# main_board_schematic.net
KiCad netlist of a schematic drawn in EasyEDA
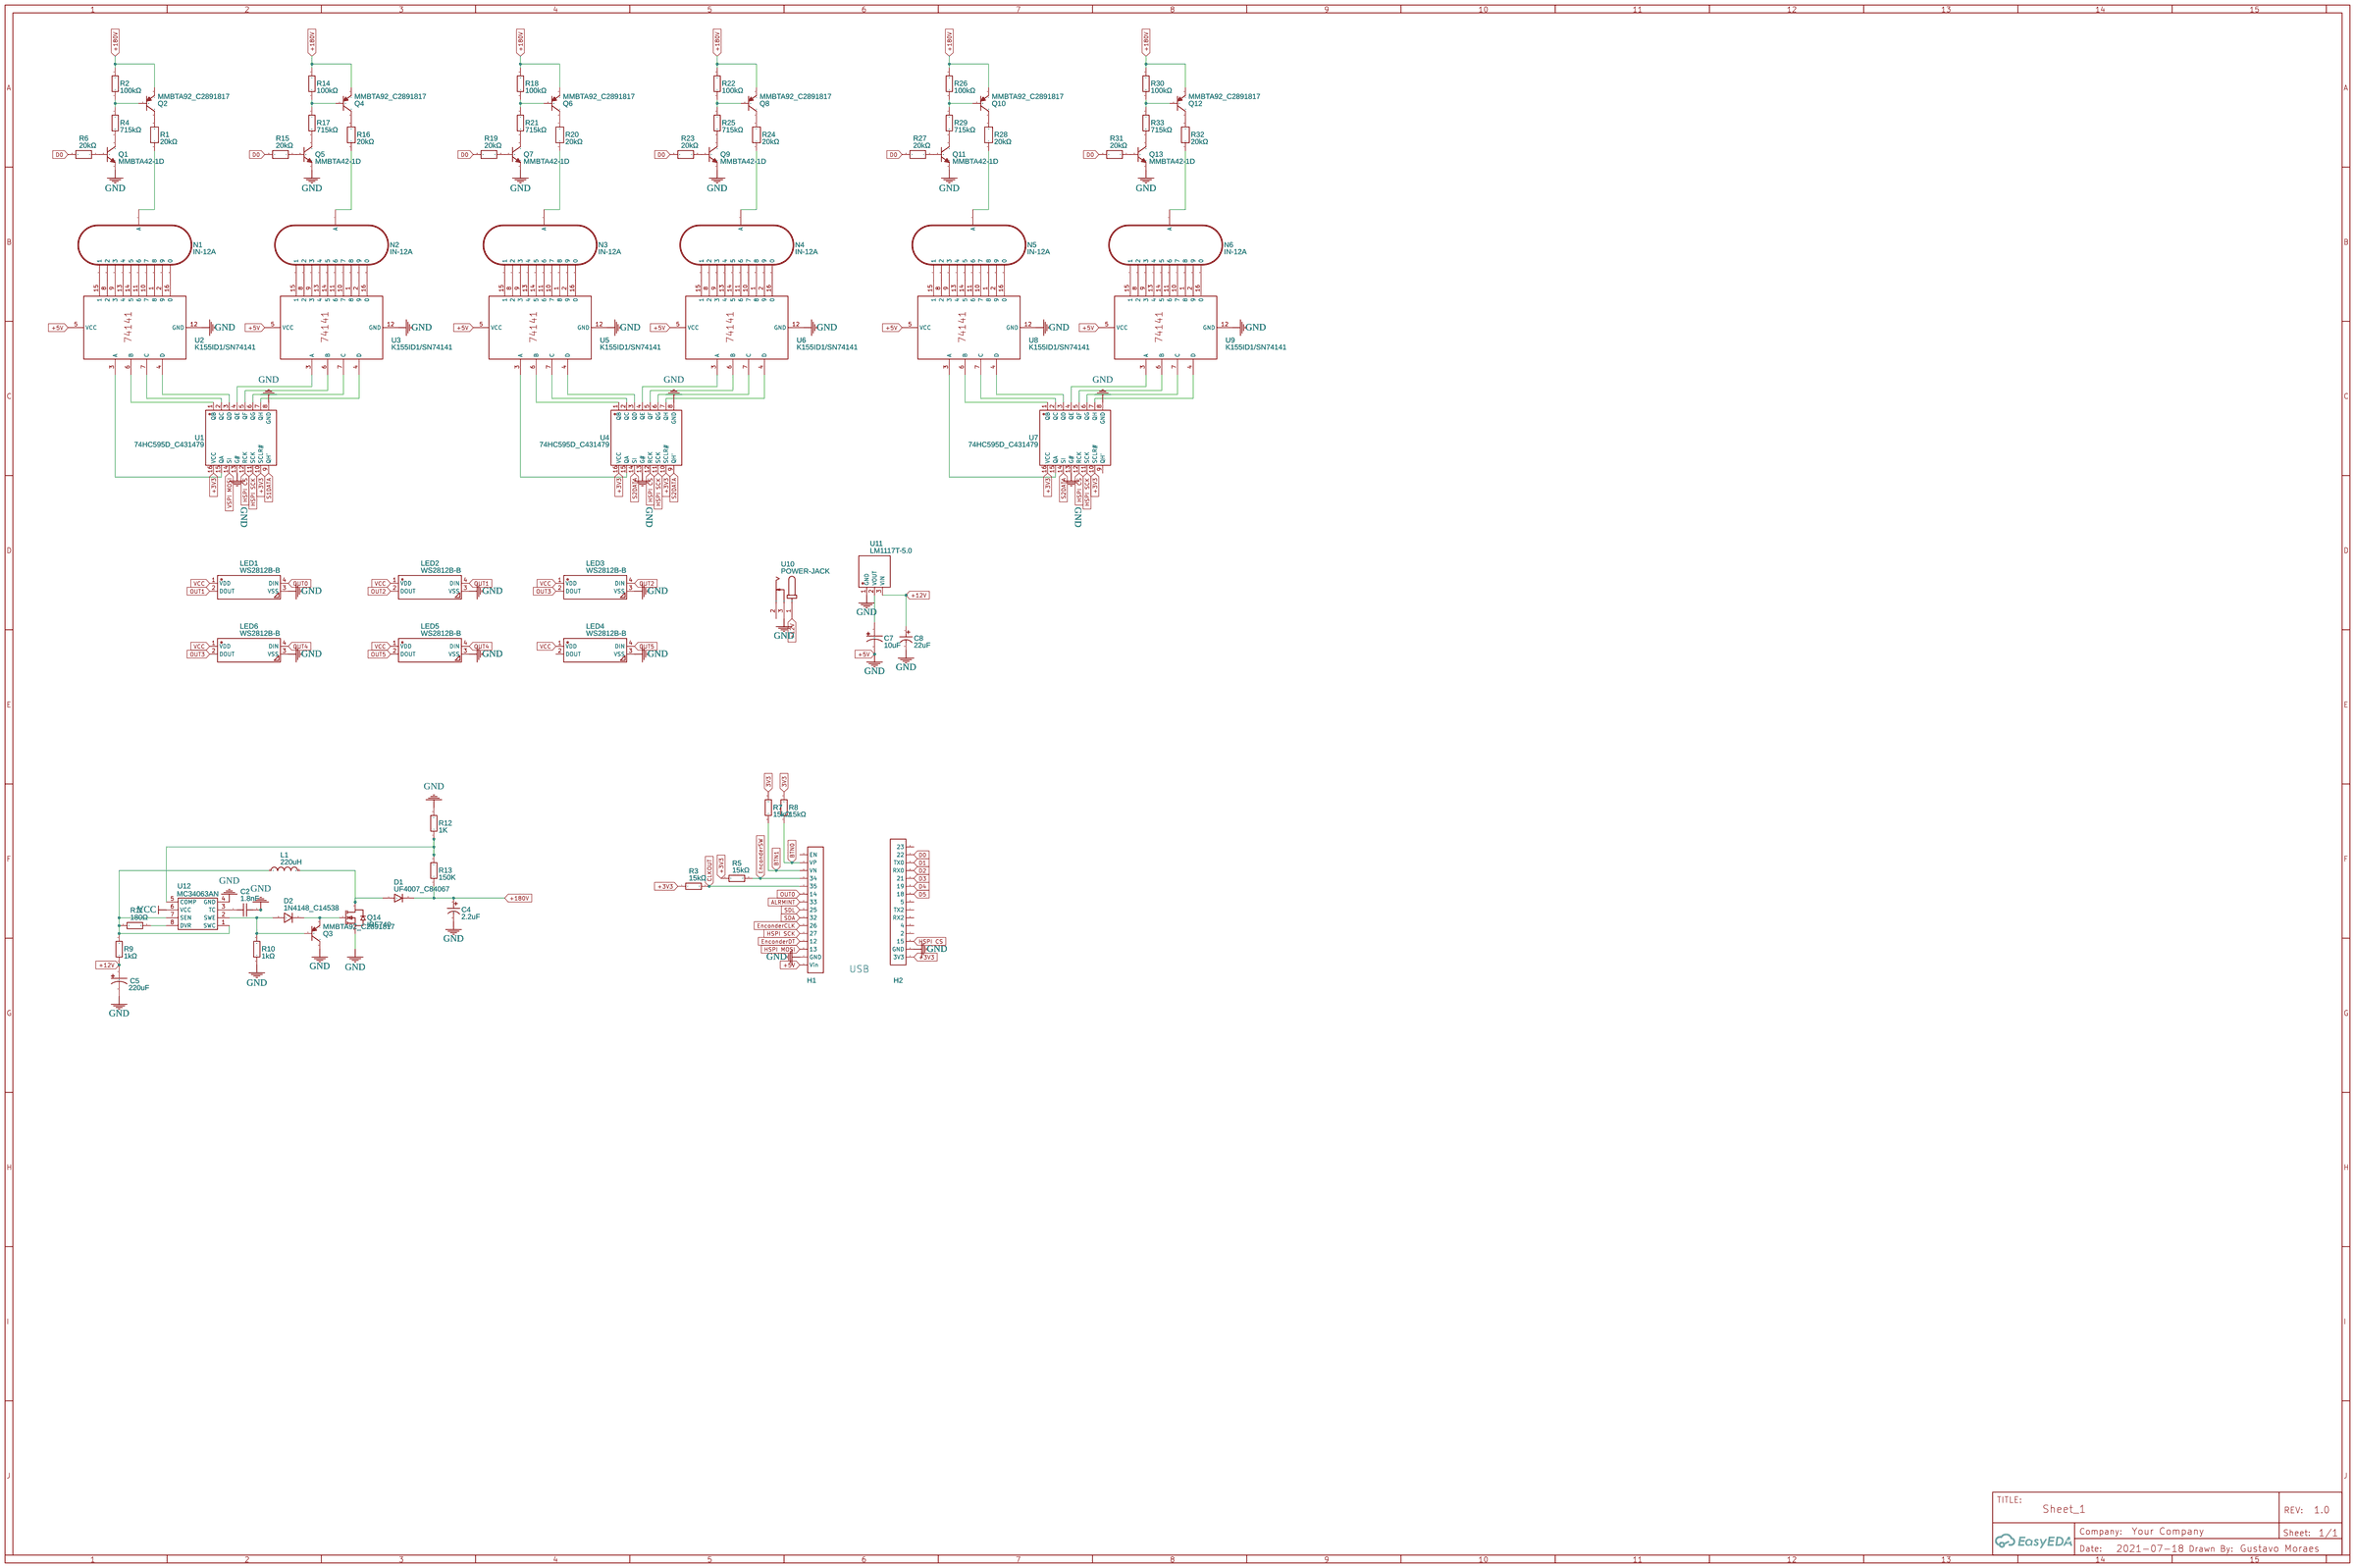
[diagram p0: schematic sheet]

(export (version "E")
  (design (tool "Eeschema 10.0.6"))
  (components
    (comp (ref "C2")
      (value "1.8nF")
      (fields
        (field (name "BOM_Manufacturer Part") "NV1206B182K102CEDN")
        (field (name "BOM_Supplier Part") "C2760344")
      )
      (libsource (lib "") (part "NV1206B182K102CEDN"))
    )
    (comp (ref "C4")
      (value "2.2uF")
      (fields
        (field (name "BOM_Manufacturer Part") "UD2E2R2M0610")
        (field (name "BOM_Supplier Part") "C98559")
      )
      (libsource (lib "") (part "UD2E2R2M0610"))
    )
    (comp (ref "C5")
      (value "220uF")
      (fields
        (field (name "BOM_Manufacturer Part") "RT1E221M0810")
        (field (name "BOM_Supplier Part") "C280403")
      )
      (libsource (lib "") (part "RT1E221M0810"))
    )
    (comp (ref "C7")
      (value "10uF")
      (fields
        (field (name "BOM_Manufacturer Part") "UWX1C100MCL2GB")
        (field (name "BOM_Supplier Part") "C250999")
      )
      (libsource (lib "") (part "UWX1C100MCL2GB"))
    )
    (comp (ref "C8")
      (value "22uF")
      (fields
        (field (name "BOM_Manufacturer Part") "RVT1C220M0405")
        (field (name "BOM_Supplier Part") "C72502")
      )
      (libsource (lib "") (part "RVT1C220M0405"))
    )
    (comp (ref "D1")
      (value "UF4007_C84067")
      (fields (field (name "BOM_Manufacturer Part") "UF4007") (field (name "BOM_Supplier Part") "C84067"))
      (libsource (lib "") (part "UF4007_C84067"))
    )
    (comp (ref "D2")
      (value "1N4148_C14538")
      (fields (field (name "BOM_Manufacturer Part") "1N4148") (field (name "BOM_Supplier Part") "C14538"))
      (libsource (lib "") (part "1N4148_C14538"))
    )
    (comp (ref "H1")
      (value "HDR-F-2.54_1x15")
      (fields (field (name "BOM_Supplier Part") "C124408"))
      (libsource (lib "") (part "HDR-F-2.54_1x15_1"))
    )
    (comp (ref "H2")
      (value "HDR-F-2.54_1x15")
      (fields (field (name "BOM_Supplier Part") "C124408"))
      (libsource (lib "") (part "HDR-F-2.54_1x15"))
    )
    (comp (ref "L1")
      (value "220uH")
      (fields
        (field (name "BOM_Manufacturer Part") "SLH1207S221MTT")
        (field (name "BOM_Supplier Part") "C182174")
      )
      (libsource (lib "") (part "SLH1207S221MTT"))
    )
    (comp (ref "LED1")
      (value "WS2812B-B")
      (fields (field (name "BOM_Supplier Part") "C114586"))
      (libsource (lib "") (part "WS2812B-B"))
    )
    (comp (ref "LED2")
      (value "WS2812B-B")
      (fields (field (name "BOM_Supplier Part") "C114586"))
      (libsource (lib "") (part "WS2812B-B"))
    )
    (comp (ref "LED3")
      (value "WS2812B-B")
      (fields (field (name "BOM_Supplier Part") "C114586"))
      (libsource (lib "") (part "WS2812B-B"))
    )
    (comp (ref "LED4")
      (value "WS2812B-B")
      (fields (field (name "BOM_Supplier Part") "C114586"))
      (libsource (lib "") (part "WS2812B-B"))
    )
    (comp (ref "LED5")
      (value "WS2812B-B")
      (fields (field (name "BOM_Supplier Part") "C114586"))
      (libsource (lib "") (part "WS2812B-B"))
    )
    (comp (ref "LED6")
      (value "WS2812B-B")
      (fields (field (name "BOM_Supplier Part") "C114586"))
      (libsource (lib "") (part "WS2812B-B"))
    )
    (comp (ref "N1") (value "IN-12A") (libsource (lib "") (part "IN-12A")))
    (comp (ref "N2") (value "IN-12A") (libsource (lib "") (part "IN-12A")))
    (comp (ref "N3") (value "IN-12A") (libsource (lib "") (part "IN-12A")))
    (comp (ref "N4") (value "IN-12A") (libsource (lib "") (part "IN-12A")))
    (comp (ref "N5") (value "IN-12A") (libsource (lib "") (part "IN-12A")))
    (comp (ref "N6") (value "IN-12A") (libsource (lib "") (part "IN-12A")))
    (comp (ref "Q1")
      (value "MMBTA42-1D")
      (fields (field (name "BOM_Supplier Part") "C779717"))
      (libsource (lib "") (part "MMBTA42-1D"))
    )
    (comp (ref "Q2")
      (value "MMBTA92_C2891817")
      (fields (field (name "BOM_Manufacturer Part") "MMBTA92") (field (name "BOM_Supplier Part") "C2891817"))
      (libsource (lib "") (part "MMBTA92_C2891817"))
    )
    (comp (ref "Q3")
      (value "MMBTA92_C2891817")
      (fields (field (name "BOM_Manufacturer Part") "MMBTA92") (field (name "BOM_Supplier Part") "C2891817"))
      (libsource (lib "") (part "MMBTA92_C2891817"))
    )
    (comp (ref "Q4")
      (value "MMBTA92_C2891817")
      (fields (field (name "BOM_Manufacturer Part") "MMBTA92") (field (name "BOM_Supplier Part") "C2891817"))
      (libsource (lib "") (part "MMBTA92_C2891817"))
    )
    (comp (ref "Q5")
      (value "MMBTA42-1D")
      (fields (field (name "BOM_Supplier Part") "C779717"))
      (libsource (lib "") (part "MMBTA42-1D"))
    )
    (comp (ref "Q6")
      (value "MMBTA92_C2891817")
      (fields (field (name "BOM_Manufacturer Part") "MMBTA92") (field (name "BOM_Supplier Part") "C2891817"))
      (libsource (lib "") (part "MMBTA92_C2891817"))
    )
    (comp (ref "Q7")
      (value "MMBTA42-1D")
      (fields (field (name "BOM_Supplier Part") "C779717"))
      (libsource (lib "") (part "MMBTA42-1D"))
    )
    (comp (ref "Q8")
      (value "MMBTA92_C2891817")
      (fields (field (name "BOM_Manufacturer Part") "MMBTA92") (field (name "BOM_Supplier Part") "C2891817"))
      (libsource (lib "") (part "MMBTA92_C2891817"))
    )
    (comp (ref "Q9")
      (value "MMBTA42-1D")
      (fields (field (name "BOM_Supplier Part") "C779717"))
      (libsource (lib "") (part "MMBTA42-1D"))
    )
    (comp (ref "Q10")
      (value "MMBTA92_C2891817")
      (fields (field (name "BOM_Manufacturer Part") "MMBTA92") (field (name "BOM_Supplier Part") "C2891817"))
      (libsource (lib "") (part "MMBTA92_C2891817"))
    )
    (comp (ref "Q11")
      (value "MMBTA42-1D")
      (fields (field (name "BOM_Supplier Part") "C779717"))
      (libsource (lib "") (part "MMBTA42-1D"))
    )
    (comp (ref "Q12")
      (value "MMBTA92_C2891817")
      (fields (field (name "BOM_Manufacturer Part") "MMBTA92") (field (name "BOM_Supplier Part") "C2891817"))
      (libsource (lib "") (part "MMBTA92_C2891817"))
    )
    (comp (ref "Q13")
      (value "MMBTA42-1D")
      (fields (field (name "BOM_Supplier Part") "C779717"))
      (libsource (lib "") (part "MMBTA42-1D"))
    )
    (comp (ref "Q14")
      (value "IRF740")
      (fields (field (name "BOM_Supplier Part") "C358408"))
      (libsource (lib "") (part "IRF740"))
    )
    (comp (ref "R1")
      (value "20kΩ")
      (fields
        (field (name "BOM_Manufacturer Part") "ERJ6GEYJ203V")
        (field (name "BOM_Supplier Part") "C413204")
      )
      (libsource (lib "") (part "ERJ6GEYJ203V"))
    )
    (comp (ref "R2")
      (value "100kΩ")
      (fields
        (field (name "BOM_Manufacturer Part") "ERJ6RBD1003V")
        (field (name "BOM_Supplier Part") "C336855")
      )
      (libsource (lib "") (part "ERJ6RBD1003V"))
    )
    (comp (ref "R3")
      (value "15kΩ")
      (fields
        (field (name "BOM_Manufacturer Part") "ERJ-6ENF1502V")
        (field (name "BOM_Supplier Part") "C192065")
      )
      (libsource (lib "") (part "ERJ-6ENF1502V_1"))
    )
    (comp (ref "R4")
      (value "715kΩ")
      (fields
        (field (name "BOM_Manufacturer Part") "CR1206F715KP05")
        (field (name "BOM_Supplier Part") "C245593")
      )
      (libsource (lib "") (part "CR1206F715KP05"))
    )
    (comp (ref "R5")
      (value "15kΩ")
      (fields
        (field (name "BOM_Manufacturer Part") "ERJ-6ENF1502V")
        (field (name "BOM_Supplier Part") "C192065")
      )
      (libsource (lib "") (part "ERJ-6ENF1502V_1"))
    )
    (comp (ref "R6")
      (value "20kΩ")
      (fields
        (field (name "BOM_Manufacturer Part") "ERJ6GEYJ203V")
        (field (name "BOM_Supplier Part") "C413204")
      )
      (libsource (lib "") (part "ERJ6GEYJ203V_1"))
    )
    (comp (ref "R7")
      (value "15kΩ")
      (fields
        (field (name "BOM_Manufacturer Part") "ERJ-6ENF1502V")
        (field (name "BOM_Supplier Part") "C192065")
      )
      (libsource (lib "") (part "ERJ-6ENF1502V"))
    )
    (comp (ref "R8")
      (value "15kΩ")
      (fields
        (field (name "BOM_Manufacturer Part") "ERJ-6ENF1502V")
        (field (name "BOM_Supplier Part") "C192065")
      )
      (libsource (lib "") (part "ERJ-6ENF1502V"))
    )
    (comp (ref "R9")
      (value "1kΩ")
      (fields
        (field (name "BOM_Manufacturer Part") "AECR1206F1K00K9")
        (field (name "BOM_Supplier Part") "C328410")
      )
      (libsource (lib "") (part "AECR1206F1K00K9"))
    )
    (comp (ref "R10")
      (value "1kΩ")
      (fields
        (field (name "BOM_Manufacturer Part") "AECR1206F1K00K9")
        (field (name "BOM_Supplier Part") "C328410")
      )
      (libsource (lib "") (part "AECR1206F1K00K9"))
    )
    (comp (ref "R11")
      (value "180Ω")
      (fields
        (field (name "BOM_Manufacturer Part") "QR1206J180RP05")
        (field (name "BOM_Supplier Part") "C149884")
      )
      (libsource (lib "") (part "QR1206J180RP05"))
    )
    (comp (ref "R12")
      (value "1K")
      (fields
        (field (name "BOM_Manufacturer Part") "MFR0W4F1001A50")
        (field (name "BOM_Supplier Part") "C57435")
      )
      (libsource (lib "") (part "MFR0W4F1001A50"))
    )
    (comp (ref "R13")
      (value "150K")
      (fields
        (field (name "BOM_Manufacturer Part") "MFR0W4F1503A50")
        (field (name "BOM_Supplier Part") "C58618")
      )
      (libsource (lib "") (part "MFR0W4F1503A50"))
    )
    (comp (ref "R14")
      (value "100kΩ")
      (fields
        (field (name "BOM_Manufacturer Part") "ERJ6RBD1003V")
        (field (name "BOM_Supplier Part") "C336855")
      )
      (libsource (lib "") (part "ERJ6RBD1003V"))
    )
    (comp (ref "R15")
      (value "20kΩ")
      (fields
        (field (name "BOM_Manufacturer Part") "ERJ6GEYJ203V")
        (field (name "BOM_Supplier Part") "C413204")
      )
      (libsource (lib "") (part "ERJ6GEYJ203V_1"))
    )
    (comp (ref "R16")
      (value "20kΩ")
      (fields
        (field (name "BOM_Manufacturer Part") "ERJ6GEYJ203V")
        (field (name "BOM_Supplier Part") "C413204")
      )
      (libsource (lib "") (part "ERJ6GEYJ203V"))
    )
    (comp (ref "R17")
      (value "715kΩ")
      (fields
        (field (name "BOM_Manufacturer Part") "CR1206F715KP05")
        (field (name "BOM_Supplier Part") "C245593")
      )
      (libsource (lib "") (part "CR1206F715KP05"))
    )
    (comp (ref "R18")
      (value "100kΩ")
      (fields
        (field (name "BOM_Manufacturer Part") "ERJ6RBD1003V")
        (field (name "BOM_Supplier Part") "C336855")
      )
      (libsource (lib "") (part "ERJ6RBD1003V"))
    )
    (comp (ref "R19")
      (value "20kΩ")
      (fields
        (field (name "BOM_Manufacturer Part") "ERJ6GEYJ203V")
        (field (name "BOM_Supplier Part") "C413204")
      )
      (libsource (lib "") (part "ERJ6GEYJ203V_1"))
    )
    (comp (ref "R20")
      (value "20kΩ")
      (fields
        (field (name "BOM_Manufacturer Part") "ERJ6GEYJ203V")
        (field (name "BOM_Supplier Part") "C413204")
      )
      (libsource (lib "") (part "ERJ6GEYJ203V"))
    )
    (comp (ref "R21")
      (value "715kΩ")
      (fields
        (field (name "BOM_Manufacturer Part") "CR1206F715KP05")
        (field (name "BOM_Supplier Part") "C245593")
      )
      (libsource (lib "") (part "CR1206F715KP05"))
    )
    (comp (ref "R22")
      (value "100kΩ")
      (fields
        (field (name "BOM_Manufacturer Part") "ERJ6RBD1003V")
        (field (name "BOM_Supplier Part") "C336855")
      )
      (libsource (lib "") (part "ERJ6RBD1003V"))
    )
    (comp (ref "R23")
      (value "20kΩ")
      (fields
        (field (name "BOM_Manufacturer Part") "ERJ6GEYJ203V")
        (field (name "BOM_Supplier Part") "C413204")
      )
      (libsource (lib "") (part "ERJ6GEYJ203V_1"))
    )
    (comp (ref "R24")
      (value "20kΩ")
      (fields
        (field (name "BOM_Manufacturer Part") "ERJ6GEYJ203V")
        (field (name "BOM_Supplier Part") "C413204")
      )
      (libsource (lib "") (part "ERJ6GEYJ203V"))
    )
    (comp (ref "R25")
      (value "715kΩ")
      (fields
        (field (name "BOM_Manufacturer Part") "CR1206F715KP05")
        (field (name "BOM_Supplier Part") "C245593")
      )
      (libsource (lib "") (part "CR1206F715KP05"))
    )
    (comp (ref "R26")
      (value "100kΩ")
      (fields
        (field (name "BOM_Manufacturer Part") "ERJ6RBD1003V")
        (field (name "BOM_Supplier Part") "C336855")
      )
      (libsource (lib "") (part "ERJ6RBD1003V"))
    )
    (comp (ref "R27")
      (value "20kΩ")
      (fields
        (field (name "BOM_Manufacturer Part") "ERJ6GEYJ203V")
        (field (name "BOM_Supplier Part") "C413204")
      )
      (libsource (lib "") (part "ERJ6GEYJ203V_1"))
    )
    (comp (ref "R28")
      (value "20kΩ")
      (fields
        (field (name "BOM_Manufacturer Part") "ERJ6GEYJ203V")
        (field (name "BOM_Supplier Part") "C413204")
      )
      (libsource (lib "") (part "ERJ6GEYJ203V"))
    )
    (comp (ref "R29")
      (value "715kΩ")
      (fields
        (field (name "BOM_Manufacturer Part") "CR1206F715KP05")
        (field (name "BOM_Supplier Part") "C245593")
      )
      (libsource (lib "") (part "CR1206F715KP05"))
    )
    (comp (ref "R30")
      (value "100kΩ")
      (fields
        (field (name "BOM_Manufacturer Part") "ERJ6RBD1003V")
        (field (name "BOM_Supplier Part") "C336855")
      )
      (libsource (lib "") (part "ERJ6RBD1003V"))
    )
    (comp (ref "R31")
      (value "20kΩ")
      (fields
        (field (name "BOM_Manufacturer Part") "ERJ6GEYJ203V")
        (field (name "BOM_Supplier Part") "C413204")
      )
      (libsource (lib "") (part "ERJ6GEYJ203V_1"))
    )
    (comp (ref "R32")
      (value "20kΩ")
      (fields
        (field (name "BOM_Manufacturer Part") "ERJ6GEYJ203V")
        (field (name "BOM_Supplier Part") "C413204")
      )
      (libsource (lib "") (part "ERJ6GEYJ203V"))
    )
    (comp (ref "R33")
      (value "715kΩ")
      (fields
        (field (name "BOM_Manufacturer Part") "CR1206F715KP05")
        (field (name "BOM_Supplier Part") "C245593")
      )
      (libsource (lib "") (part "CR1206F715KP05"))
    )
    (comp (ref "U1")
      (value "74HC595D_C431479")
      (fields (field (name "BOM_Manufacturer Part") "74HC595D") (field (name "BOM_Supplier Part") "C431479"))
      (libsource (lib "") (part "74HC595D_C431479"))
    )
    (comp (ref "U2") (value "K155ID1/SN74141") (libsource (lib "") (part "K155ID1/SN74141")))
    (comp (ref "U3") (value "K155ID1/SN74141") (libsource (lib "") (part "K155ID1/SN74141")))
    (comp (ref "U4")
      (value "74HC595D_C431479")
      (fields (field (name "BOM_Manufacturer Part") "74HC595D") (field (name "BOM_Supplier Part") "C431479"))
      (libsource (lib "") (part "74HC595D_C431479"))
    )
    (comp (ref "U5") (value "K155ID1/SN74141") (libsource (lib "") (part "K155ID1/SN74141")))
    (comp (ref "U6") (value "K155ID1/SN74141") (libsource (lib "") (part "K155ID1/SN74141")))
    (comp (ref "U7")
      (value "74HC595D_C431479")
      (fields (field (name "BOM_Manufacturer Part") "74HC595D") (field (name "BOM_Supplier Part") "C431479"))
      (libsource (lib "") (part "74HC595D_C431479"))
    )
    (comp (ref "U8") (value "K155ID1/SN74141") (libsource (lib "") (part "K155ID1/SN74141")))
    (comp (ref "U9") (value "K155ID1/SN74141") (libsource (lib "") (part "K155ID1/SN74141")))
    (comp (ref "U10")
      (value "POWER-JACK")
      (fields (field (name "BOM_Supplier Part") "C9900001795"))
      (libsource (lib "") (part "POWER-JACK"))
    )
    (comp (ref "U11")
      (value "LM1117T-5.0")
      (fields (field (name "BOM_Supplier Part") "C498320"))
      (libsource (lib "") (part "LM1117T-5.0"))
    )
    (comp (ref "U12")
      (value "MC34063AN")
      (fields (field (name "BOM_Supplier Part") "C126078"))
      (libsource (lib "") (part "MC34063AN"))
    )
  )
  (nets
    (net (code "1") (name "+3V3") (class "Default")
      (node (ref "H2") (pin "1") (pinfunction "3V3_1") (pintype "unspecified"))
      (node (ref "R3") (pin "1") (pinfunction "1_1") (pintype "unspecified"))
      (node (ref "R5") (pin "1") (pinfunction "1_1") (pintype "unspecified"))
      (node (ref "U1") (pin "10") (pinfunction "SCLR#_10") (pintype "unspecified"))
      (node (ref "U1") (pin "16") (pinfunction "VCC_16") (pintype "unspecified"))
      (node (ref "U4") (pin "10") (pinfunction "SCLR#_10") (pintype "unspecified"))
      (node (ref "U4") (pin "16") (pinfunction "VCC_16") (pintype "unspecified"))
      (node (ref "U7") (pin "10") (pinfunction "SCLR#_10") (pintype "unspecified"))
      (node (ref "U7") (pin "16") (pinfunction "VCC_16") (pintype "unspecified"))
    )
    (net (code "2") (name "+5V") (class "Default")
      (node (ref "C2") (pin "2") (pinfunction "2_2") (pintype "unspecified"))
      (node (ref "C4") (pin "2") (pinfunction "2_2") (pintype "input"))
      (node (ref "C5") (pin "2") (pinfunction "2_2") (pintype "unspecified"))
      (node (ref "C7") (pin "2") (pinfunction "2_2") (pintype "unspecified"))
      (node (ref "C8") (pin "2") (pinfunction "2_2") (pintype "input"))
      (node (ref "H1") (pin "1") (pinfunction "Vin_1") (pintype "unspecified"))
      (node (ref "H1") (pin "2") (pinfunction "GND_2") (pintype "unspecified"))
      (node (ref "H2") (pin "2") (pinfunction "GND_2") (pintype "unspecified"))
      (node (ref "LED1") (pin "3") (pinfunction "VSS_3") (pintype "unspecified"))
      (node (ref "LED2") (pin "3") (pinfunction "VSS_3") (pintype "unspecified"))
      (node (ref "LED3") (pin "3") (pinfunction "VSS_3") (pintype "unspecified"))
      (node (ref "LED4") (pin "3") (pinfunction "VSS_3") (pintype "unspecified"))
      (node (ref "LED5") (pin "3") (pinfunction "VSS_3") (pintype "unspecified"))
      (node (ref "LED6") (pin "3") (pinfunction "VSS_3") (pintype "unspecified"))
      (node (ref "Q1") (pin "2") (pinfunction "E_2") (pintype "unspecified"))
      (node (ref "Q11") (pin "2") (pinfunction "E_2") (pintype "unspecified"))
      (node (ref "Q13") (pin "2") (pinfunction "E_2") (pintype "unspecified"))
      (node (ref "Q14") (pin "3") (pinfunction "S_3") (pintype "unspecified"))
      (node (ref "Q3") (pin "3") (pinfunction "C_3") (pintype "input"))
      (node (ref "Q5") (pin "2") (pinfunction "E_2") (pintype "unspecified"))
      (node (ref "Q7") (pin "2") (pinfunction "E_2") (pintype "unspecified"))
      (node (ref "Q9") (pin "2") (pinfunction "E_2") (pintype "unspecified"))
      (node (ref "R10") (pin "1") (pinfunction "1_1") (pintype "unspecified"))
      (node (ref "R12") (pin "2") (pinfunction "2_2") (pintype "input"))
      (node (ref "U1") (pin "13") (pinfunction "G#_13") (pintype "unspecified"))
      (node (ref "U1") (pin "8") (pinfunction "GND_8") (pintype "unspecified"))
      (node (ref "U10") (pin "3") (pinfunction "3_3") (pintype "unspecified"))
      (node (ref "U11") (pin "1") (pinfunction "GND_1") (pintype "unspecified"))
      (node (ref "U12") (pin "4") (pinfunction "GND_4") (pintype "unspecified"))
      (node (ref "U2") (pin "12") (pinfunction "GND_12") (pintype "passive"))
      (node (ref "U2") (pin "5") (pinfunction "VCC_5") (pintype "passive"))
      (node (ref "U3") (pin "12") (pinfunction "GND_12") (pintype "passive"))
      (node (ref "U3") (pin "5") (pinfunction "VCC_5") (pintype "passive"))
      (node (ref "U4") (pin "13") (pinfunction "G#_13") (pintype "unspecified"))
      (node (ref "U4") (pin "8") (pinfunction "GND_8") (pintype "unspecified"))
      (node (ref "U5") (pin "12") (pinfunction "GND_12") (pintype "passive"))
      (node (ref "U5") (pin "5") (pinfunction "VCC_5") (pintype "passive"))
      (node (ref "U6") (pin "12") (pinfunction "GND_12") (pintype "passive"))
      (node (ref "U6") (pin "5") (pinfunction "VCC_5") (pintype "passive"))
      (node (ref "U7") (pin "13") (pinfunction "G#_13") (pintype "unspecified"))
      (node (ref "U7") (pin "8") (pinfunction "GND_8") (pintype "unspecified"))
      (node (ref "U8") (pin "12") (pinfunction "GND_12") (pintype "passive"))
      (node (ref "U8") (pin "5") (pinfunction "VCC_5") (pintype "passive"))
      (node (ref "U9") (pin "12") (pinfunction "GND_12") (pintype "passive"))
      (node (ref "U9") (pin "5") (pinfunction "VCC_5") (pintype "passive"))
    )
    (net (code "3") (name "+12V") (class "Default")
      (node (ref "C5") (pin "1") (pinfunction "1_1") (pintype "unspecified"))
      (node (ref "C8") (pin "1") (pinfunction "1_1") (pintype "input"))
      (node (ref "R9") (pin "1") (pinfunction "1_1") (pintype "unspecified"))
      (node (ref "U10") (pin "1") (pinfunction "1_1") (pintype "unspecified"))
      (node (ref "U11") (pin "3") (pinfunction "VIN_3") (pintype "unspecified"))
    )
    (net (code "4") (name "+180V") (class "Default")
      (node (ref "C4") (pin "1") (pinfunction "1_1") (pintype "input"))
      (node (ref "D1") (pin "2") (pinfunction "C_2") (pintype "unspecified"))
      (node (ref "Q10") (pin "2") (pinfunction "E_2") (pintype "input"))
      (node (ref "Q12") (pin "2") (pinfunction "E_2") (pintype "input"))
      (node (ref "Q2") (pin "2") (pinfunction "E_2") (pintype "input"))
      (node (ref "Q4") (pin "2") (pinfunction "E_2") (pintype "input"))
      (node (ref "Q6") (pin "2") (pinfunction "E_2") (pintype "input"))
      (node (ref "Q8") (pin "2") (pinfunction "E_2") (pintype "input"))
      (node (ref "R13") (pin "1") (pinfunction "1_1") (pintype "input"))
      (node (ref "R14") (pin "1") (pinfunction "1_1") (pintype "unspecified"))
      (node (ref "R18") (pin "1") (pinfunction "1_1") (pintype "unspecified"))
      (node (ref "R2") (pin "1") (pinfunction "1_1") (pintype "unspecified"))
      (node (ref "R22") (pin "1") (pinfunction "1_1") (pintype "unspecified"))
      (node (ref "R26") (pin "1") (pinfunction "1_1") (pintype "unspecified"))
      (node (ref "R30") (pin "1") (pinfunction "1_1") (pintype "unspecified"))
    )
    (net (code "5") (name "3V3") (class "Default")
      (node (ref "R7") (pin "2") (pinfunction "2_2") (pintype "unspecified"))
      (node (ref "R8") (pin "2") (pinfunction "2_2") (pintype "unspecified"))
    )
    (net (code "6") (name "ALRMINT") (class "Default")
      (node (ref "H1") (pin "9") (pinfunction "33_9") (pintype "unspecified"))
    )
    (net (code "7") (name "BTN0") (class "Default")
      (node (ref "H1") (pin "14") (pinfunction "VP_14") (pintype "unspecified"))
      (node (ref "R8") (pin "1") (pinfunction "1_1") (pintype "unspecified"))
    )
    (net (code "8") (name "BTN1") (class "Default")
      (node (ref "H1") (pin "13") (pinfunction "VN_13") (pintype "unspecified"))
      (node (ref "R7") (pin "1") (pinfunction "1_1") (pintype "unspecified"))
    )
    (net (code "9") (name "CLKOUT") (class "Default")
      (node (ref "H1") (pin "11") (pinfunction "35_11") (pintype "unspecified"))
      (node (ref "R3") (pin "2") (pinfunction "2_2") (pintype "unspecified"))
    )
    (net (code "10") (name "D0") (class "Default")
      (node (ref "H2") (pin "14") (pinfunction "22_14") (pintype "unspecified"))
      (node (ref "R15") (pin "2") (pinfunction "2_2") (pintype "unspecified"))
      (node (ref "R19") (pin "2") (pinfunction "2_2") (pintype "unspecified"))
      (node (ref "R23") (pin "2") (pinfunction "2_2") (pintype "unspecified"))
      (node (ref "R27") (pin "2") (pinfunction "2_2") (pintype "unspecified"))
      (node (ref "R31") (pin "2") (pinfunction "2_2") (pintype "unspecified"))
      (node (ref "R6") (pin "2") (pinfunction "2_2") (pintype "unspecified"))
    )
    (net (code "11") (name "D1") (class "Default")
      (node (ref "H2") (pin "13") (pinfunction "TX0_13") (pintype "unspecified"))
    )
    (net (code "12") (name "D2") (class "Default")
      (node (ref "H2") (pin "12") (pinfunction "RX0_12") (pintype "unspecified"))
    )
    (net (code "13") (name "D3") (class "Default")
      (node (ref "H2") (pin "11") (pinfunction "21_11") (pintype "unspecified"))
    )
    (net (code "14") (name "D4") (class "Default")
      (node (ref "H2") (pin "10") (pinfunction "19_10") (pintype "unspecified"))
    )
    (net (code "15") (name "D5") (class "Default")
      (node (ref "H2") (pin "9") (pinfunction "18_9") (pintype "unspecified"))
    )
    (net (code "16") (name "EnconderCLK") (class "Default")
      (node (ref "H1") (pin "6") (pinfunction "26_6") (pintype "unspecified"))
    )
    (net (code "17") (name "EnconderDT") (class "Default")
      (node (ref "H1") (pin "4") (pinfunction "12_4") (pintype "unspecified"))
    )
    (net (code "18") (name "EnconderSW") (class "Default")
      (node (ref "H1") (pin "12") (pinfunction "34_12") (pintype "unspecified"))
      (node (ref "R5") (pin "2") (pinfunction "2_2") (pintype "unspecified"))
    )
    (net (code "19") (name "HSPI CS") (class "Default")
      (node (ref "H2") (pin "3") (pinfunction "15_3") (pintype "unspecified"))
      (node (ref "U1") (pin "12") (pinfunction "RCK_12") (pintype "unspecified"))
      (node (ref "U4") (pin "12") (pinfunction "RCK_12") (pintype "unspecified"))
      (node (ref "U7") (pin "12") (pinfunction "RCK_12") (pintype "unspecified"))
    )
    (net (code "20") (name "HSPI MOSI") (class "Default")
      (node (ref "H1") (pin "3") (pinfunction "13_3") (pintype "unspecified"))
    )
    (net (code "21") (name "HSPI SCK") (class "Default")
      (node (ref "H1") (pin "5") (pinfunction "27_5") (pintype "unspecified"))
      (node (ref "U1") (pin "11") (pinfunction "SCK_11") (pintype "unspecified"))
      (node (ref "U4") (pin "11") (pinfunction "SCK_11") (pintype "unspecified"))
      (node (ref "U7") (pin "11") (pinfunction "SCK_11") (pintype "unspecified"))
    )
    (net (code "22") (name "Net-(D1-A)") (class "Default")
      (node (ref "D1") (pin "1") (pinfunction "A_1") (pintype "unspecified"))
      (node (ref "L1") (pin "2") (pinfunction "2_2") (pintype "unspecified"))
      (node (ref "Q14") (pin "2") (pinfunction "D_2") (pintype "unspecified"))
    )
    (net (code "23") (name "Net-(N1-PadA)") (class "Default")
      (node (ref "N1") (pin "A") (pinfunction "A_A") (pintype "unspecified"))
      (node (ref "R1") (pin "1") (pinfunction "1_1") (pintype "unspecified"))
    )
    (net (code "24") (name "Net-(N2-PadA)") (class "Default")
      (node (ref "N2") (pin "A") (pinfunction "A_A") (pintype "unspecified"))
      (node (ref "R16") (pin "1") (pinfunction "1_1") (pintype "unspecified"))
    )
    (net (code "25") (name "Net-(N3-PadA)") (class "Default")
      (node (ref "N3") (pin "A") (pinfunction "A_A") (pintype "unspecified"))
      (node (ref "R20") (pin "1") (pinfunction "1_1") (pintype "unspecified"))
    )
    (net (code "26") (name "Net-(N4-PadA)") (class "Default")
      (node (ref "N4") (pin "A") (pinfunction "A_A") (pintype "unspecified"))
      (node (ref "R24") (pin "1") (pinfunction "1_1") (pintype "unspecified"))
    )
    (net (code "27") (name "Net-(N5-PadA)") (class "Default")
      (node (ref "N5") (pin "A") (pinfunction "A_A") (pintype "unspecified"))
      (node (ref "R28") (pin "1") (pinfunction "1_1") (pintype "unspecified"))
    )
    (net (code "28") (name "Net-(N6-PadA)") (class "Default")
      (node (ref "N6") (pin "A") (pinfunction "A_A") (pintype "unspecified"))
      (node (ref "R32") (pin "1") (pinfunction "1_1") (pintype "unspecified"))
    )
    (net (code "29") (name "Net-(Q1-B)") (class "Default")
      (node (ref "Q1") (pin "1") (pinfunction "B_1") (pintype "unspecified"))
      (node (ref "R6") (pin "1") (pinfunction "1_1") (pintype "unspecified"))
    )
    (net (code "30") (name "Net-(Q1-C)") (class "Default")
      (node (ref "Q1") (pin "3") (pinfunction "C_3") (pintype "unspecified"))
      (node (ref "R4") (pin "2") (pinfunction "2_2") (pintype "unspecified"))
    )
    (net (code "31") (name "Net-(Q2-B)") (class "Default")
      (node (ref "Q2") (pin "1") (pinfunction "B_1") (pintype "input"))
      (node (ref "R2") (pin "2") (pinfunction "2_2") (pintype "unspecified"))
      (node (ref "R4") (pin "1") (pinfunction "1_1") (pintype "unspecified"))
    )
    (net (code "32") (name "Net-(Q2-C)") (class "Default")
      (node (ref "Q2") (pin "3") (pinfunction "C_3") (pintype "input"))
      (node (ref "R1") (pin "2") (pinfunction "2_2") (pintype "unspecified"))
    )
    (net (code "33") (name "Net-(Q3-B)") (class "Default")
      (node (ref "D2") (pin "2") (pinfunction "2_2") (pintype "unspecified"))
      (node (ref "Q3") (pin "1") (pinfunction "B_1") (pintype "input"))
      (node (ref "R10") (pin "2") (pinfunction "2_2") (pintype "unspecified"))
      (node (ref "U12") (pin "2") (pinfunction "SWE_2") (pintype "unspecified"))
    )
    (net (code "34") (name "Net-(Q4-B)") (class "Default")
      (node (ref "Q4") (pin "1") (pinfunction "B_1") (pintype "input"))
      (node (ref "R14") (pin "2") (pinfunction "2_2") (pintype "unspecified"))
      (node (ref "R17") (pin "1") (pinfunction "1_1") (pintype "unspecified"))
    )
    (net (code "35") (name "Net-(Q4-C)") (class "Default")
      (node (ref "Q4") (pin "3") (pinfunction "C_3") (pintype "input"))
      (node (ref "R16") (pin "2") (pinfunction "2_2") (pintype "unspecified"))
    )
    (net (code "36") (name "Net-(Q5-B)") (class "Default")
      (node (ref "Q5") (pin "1") (pinfunction "B_1") (pintype "unspecified"))
      (node (ref "R15") (pin "1") (pinfunction "1_1") (pintype "unspecified"))
    )
    (net (code "37") (name "Net-(Q5-C)") (class "Default")
      (node (ref "Q5") (pin "3") (pinfunction "C_3") (pintype "unspecified"))
      (node (ref "R17") (pin "2") (pinfunction "2_2") (pintype "unspecified"))
    )
    (net (code "38") (name "Net-(Q6-B)") (class "Default")
      (node (ref "Q6") (pin "1") (pinfunction "B_1") (pintype "input"))
      (node (ref "R18") (pin "2") (pinfunction "2_2") (pintype "unspecified"))
      (node (ref "R21") (pin "1") (pinfunction "1_1") (pintype "unspecified"))
    )
    (net (code "39") (name "Net-(Q6-C)") (class "Default")
      (node (ref "Q6") (pin "3") (pinfunction "C_3") (pintype "input"))
      (node (ref "R20") (pin "2") (pinfunction "2_2") (pintype "unspecified"))
    )
    (net (code "40") (name "Net-(Q7-B)") (class "Default")
      (node (ref "Q7") (pin "1") (pinfunction "B_1") (pintype "unspecified"))
      (node (ref "R19") (pin "1") (pinfunction "1_1") (pintype "unspecified"))
    )
    (net (code "41") (name "Net-(Q7-C)") (class "Default")
      (node (ref "Q7") (pin "3") (pinfunction "C_3") (pintype "unspecified"))
      (node (ref "R21") (pin "2") (pinfunction "2_2") (pintype "unspecified"))
    )
    (net (code "42") (name "Net-(Q8-B)") (class "Default")
      (node (ref "Q8") (pin "1") (pinfunction "B_1") (pintype "input"))
      (node (ref "R22") (pin "2") (pinfunction "2_2") (pintype "unspecified"))
      (node (ref "R25") (pin "1") (pinfunction "1_1") (pintype "unspecified"))
    )
    (net (code "43") (name "Net-(Q8-C)") (class "Default")
      (node (ref "Q8") (pin "3") (pinfunction "C_3") (pintype "input"))
      (node (ref "R24") (pin "2") (pinfunction "2_2") (pintype "unspecified"))
    )
    (net (code "44") (name "Net-(Q9-B)") (class "Default")
      (node (ref "Q9") (pin "1") (pinfunction "B_1") (pintype "unspecified"))
      (node (ref "R23") (pin "1") (pinfunction "1_1") (pintype "unspecified"))
    )
    (net (code "45") (name "Net-(Q9-C)") (class "Default")
      (node (ref "Q9") (pin "3") (pinfunction "C_3") (pintype "unspecified"))
      (node (ref "R25") (pin "2") (pinfunction "2_2") (pintype "unspecified"))
    )
    (net (code "46") (name "Net-(Q10-B)") (class "Default")
      (node (ref "Q10") (pin "1") (pinfunction "B_1") (pintype "input"))
      (node (ref "R26") (pin "2") (pinfunction "2_2") (pintype "unspecified"))
      (node (ref "R29") (pin "1") (pinfunction "1_1") (pintype "unspecified"))
    )
    (net (code "47") (name "Net-(Q10-C)") (class "Default")
      (node (ref "Q10") (pin "3") (pinfunction "C_3") (pintype "input"))
      (node (ref "R28") (pin "2") (pinfunction "2_2") (pintype "unspecified"))
    )
    (net (code "48") (name "Net-(Q11-B)") (class "Default")
      (node (ref "Q11") (pin "1") (pinfunction "B_1") (pintype "unspecified"))
      (node (ref "R27") (pin "1") (pinfunction "1_1") (pintype "unspecified"))
    )
    (net (code "49") (name "Net-(Q11-C)") (class "Default")
      (node (ref "Q11") (pin "3") (pinfunction "C_3") (pintype "unspecified"))
      (node (ref "R29") (pin "2") (pinfunction "2_2") (pintype "unspecified"))
    )
    (net (code "50") (name "Net-(Q12-B)") (class "Default")
      (node (ref "Q12") (pin "1") (pinfunction "B_1") (pintype "input"))
      (node (ref "R30") (pin "2") (pinfunction "2_2") (pintype "unspecified"))
      (node (ref "R33") (pin "1") (pinfunction "1_1") (pintype "unspecified"))
    )
    (net (code "51") (name "Net-(Q12-C)") (class "Default")
      (node (ref "Q12") (pin "3") (pinfunction "C_3") (pintype "input"))
      (node (ref "R32") (pin "2") (pinfunction "2_2") (pintype "unspecified"))
    )
    (net (code "52") (name "Net-(Q13-B)") (class "Default")
      (node (ref "Q13") (pin "1") (pinfunction "B_1") (pintype "unspecified"))
      (node (ref "R31") (pin "1") (pinfunction "1_1") (pintype "unspecified"))
    )
    (net (code "53") (name "Net-(Q13-C)") (class "Default")
      (node (ref "Q13") (pin "3") (pinfunction "C_3") (pintype "unspecified"))
      (node (ref "R33") (pin "2") (pinfunction "2_2") (pintype "unspecified"))
    )
    (net (code "54") (name "Net-(Q14-G)") (class "Default")
      (node (ref "D2") (pin "1") (pinfunction "1_1") (pintype "unspecified"))
      (node (ref "Q14") (pin "1") (pinfunction "G_1") (pintype "unspecified"))
      (node (ref "Q3") (pin "2") (pinfunction "E_2") (pintype "input"))
    )
    (net (code "55") (name "Net-(U1-QA)") (class "Default")
      (node (ref "U1") (pin "15") (pinfunction "QA_15") (pintype "unspecified"))
      (node (ref "U2") (pin "3") (pinfunction "A_3") (pintype "input"))
    )
    (net (code "56") (name "Net-(U1-QB)") (class "Default")
      (node (ref "U1") (pin "1") (pinfunction "QB_1") (pintype "unspecified"))
      (node (ref "U2") (pin "6") (pinfunction "B_6") (pintype "input"))
    )
    (net (code "57") (name "Net-(U1-QC)") (class "Default")
      (node (ref "U1") (pin "2") (pinfunction "QC_2") (pintype "unspecified"))
      (node (ref "U2") (pin "7") (pinfunction "C_7") (pintype "input"))
    )
    (net (code "58") (name "Net-(U1-QD)") (class "Default")
      (node (ref "U1") (pin "3") (pinfunction "QD_3") (pintype "unspecified"))
      (node (ref "U2") (pin "4") (pinfunction "D_4") (pintype "input"))
    )
    (net (code "59") (name "Net-(U1-QE)") (class "Default")
      (node (ref "U1") (pin "4") (pinfunction "QE_4") (pintype "unspecified"))
      (node (ref "U3") (pin "3") (pinfunction "A_3") (pintype "input"))
    )
    (net (code "60") (name "Net-(U1-QF)") (class "Default")
      (node (ref "U1") (pin "5") (pinfunction "QF_5") (pintype "unspecified"))
      (node (ref "U3") (pin "6") (pinfunction "B_6") (pintype "input"))
    )
    (net (code "61") (name "Net-(U1-QG)") (class "Default")
      (node (ref "U1") (pin "6") (pinfunction "QG_6") (pintype "unspecified"))
      (node (ref "U3") (pin "7") (pinfunction "C_7") (pintype "input"))
    )
    (net (code "62") (name "Net-(U1-QH)") (class "Default")
      (node (ref "U1") (pin "7") (pinfunction "QH_7") (pintype "unspecified"))
      (node (ref "U3") (pin "4") (pinfunction "D_4") (pintype "input"))
    )
    (net (code "63") (name "Net-(U2-0)") (class "Default")
      (node (ref "N1") (pin "0") (pinfunction "0_0") (pintype "unspecified"))
      (node (ref "U2") (pin "16") (pinfunction "0_16") (pintype "output"))
    )
    (net (code "64") (name "Net-(U2-1)") (class "Default")
      (node (ref "N1") (pin "1") (pinfunction "1_1") (pintype "unspecified"))
      (node (ref "U2") (pin "15") (pinfunction "1_15") (pintype "output"))
    )
    (net (code "65") (name "Net-(U2-2)") (class "Default")
      (node (ref "N1") (pin "2") (pinfunction "2_2") (pintype "unspecified"))
      (node (ref "U2") (pin "8") (pinfunction "2_8") (pintype "output"))
    )
    (net (code "66") (name "Net-(U2-3)") (class "Default")
      (node (ref "N1") (pin "3") (pinfunction "3_3") (pintype "unspecified"))
      (node (ref "U2") (pin "9") (pinfunction "3_9") (pintype "output"))
    )
    (net (code "67") (name "Net-(U2-4)") (class "Default")
      (node (ref "N1") (pin "4") (pinfunction "4_4") (pintype "unspecified"))
      (node (ref "U2") (pin "13") (pinfunction "4_13") (pintype "output"))
    )
    (net (code "68") (name "Net-(U2-5)") (class "Default")
      (node (ref "N1") (pin "5") (pinfunction "5_5") (pintype "unspecified"))
      (node (ref "U2") (pin "14") (pinfunction "5_14") (pintype "output"))
    )
    (net (code "69") (name "Net-(U2-6)") (class "Default")
      (node (ref "N1") (pin "6") (pinfunction "6_6") (pintype "unspecified"))
      (node (ref "U2") (pin "11") (pinfunction "6_11") (pintype "output"))
    )
    (net (code "70") (name "Net-(U2-7)") (class "Default")
      (node (ref "N1") (pin "7") (pinfunction "7_7") (pintype "unspecified"))
      (node (ref "U2") (pin "10") (pinfunction "7_10") (pintype "output"))
    )
    (net (code "71") (name "Net-(U2-8)") (class "Default")
      (node (ref "N1") (pin "8") (pinfunction "8_8") (pintype "unspecified"))
      (node (ref "U2") (pin "1") (pinfunction "8_1") (pintype "output"))
    )
    (net (code "72") (name "Net-(U2-9)") (class "Default")
      (node (ref "N1") (pin "9") (pinfunction "9_9") (pintype "unspecified"))
      (node (ref "U2") (pin "2") (pinfunction "9_2") (pintype "output"))
    )
    (net (code "73") (name "Net-(U3-0)") (class "Default")
      (node (ref "N2") (pin "0") (pinfunction "0_0") (pintype "unspecified"))
      (node (ref "U3") (pin "16") (pinfunction "0_16") (pintype "output"))
    )
    (net (code "74") (name "Net-(U3-1)") (class "Default")
      (node (ref "N2") (pin "1") (pinfunction "1_1") (pintype "unspecified"))
      (node (ref "U3") (pin "15") (pinfunction "1_15") (pintype "output"))
    )
    (net (code "75") (name "Net-(U3-2)") (class "Default")
      (node (ref "N2") (pin "2") (pinfunction "2_2") (pintype "unspecified"))
      (node (ref "U3") (pin "8") (pinfunction "2_8") (pintype "output"))
    )
    (net (code "76") (name "Net-(U3-3)") (class "Default")
      (node (ref "N2") (pin "3") (pinfunction "3_3") (pintype "unspecified"))
      (node (ref "U3") (pin "9") (pinfunction "3_9") (pintype "output"))
    )
    (net (code "77") (name "Net-(U3-4)") (class "Default")
      (node (ref "N2") (pin "4") (pinfunction "4_4") (pintype "unspecified"))
      (node (ref "U3") (pin "13") (pinfunction "4_13") (pintype "output"))
    )
    (net (code "78") (name "Net-(U3-5)") (class "Default")
      (node (ref "N2") (pin "5") (pinfunction "5_5") (pintype "unspecified"))
      (node (ref "U3") (pin "14") (pinfunction "5_14") (pintype "output"))
    )
    (net (code "79") (name "Net-(U3-6)") (class "Default")
      (node (ref "N2") (pin "6") (pinfunction "6_6") (pintype "unspecified"))
      (node (ref "U3") (pin "11") (pinfunction "6_11") (pintype "output"))
    )
    (net (code "80") (name "Net-(U3-7)") (class "Default")
      (node (ref "N2") (pin "7") (pinfunction "7_7") (pintype "unspecified"))
      (node (ref "U3") (pin "10") (pinfunction "7_10") (pintype "output"))
    )
    (net (code "81") (name "Net-(U3-8)") (class "Default")
      (node (ref "N2") (pin "8") (pinfunction "8_8") (pintype "unspecified"))
      (node (ref "U3") (pin "1") (pinfunction "8_1") (pintype "output"))
    )
    (net (code "82") (name "Net-(U3-9)") (class "Default")
      (node (ref "N2") (pin "9") (pinfunction "9_9") (pintype "unspecified"))
      (node (ref "U3") (pin "2") (pinfunction "9_2") (pintype "output"))
    )
    (net (code "83") (name "Net-(U4-QA)") (class "Default")
      (node (ref "U4") (pin "15") (pinfunction "QA_15") (pintype "unspecified"))
      (node (ref "U5") (pin "3") (pinfunction "A_3") (pintype "input"))
    )
    (net (code "84") (name "Net-(U4-QB)") (class "Default")
      (node (ref "U4") (pin "1") (pinfunction "QB_1") (pintype "unspecified"))
      (node (ref "U5") (pin "6") (pinfunction "B_6") (pintype "input"))
    )
    (net (code "85") (name "Net-(U4-QC)") (class "Default")
      (node (ref "U4") (pin "2") (pinfunction "QC_2") (pintype "unspecified"))
      (node (ref "U5") (pin "7") (pinfunction "C_7") (pintype "input"))
    )
    (net (code "86") (name "Net-(U4-QD)") (class "Default")
      (node (ref "U4") (pin "3") (pinfunction "QD_3") (pintype "unspecified"))
      (node (ref "U5") (pin "4") (pinfunction "D_4") (pintype "input"))
    )
    (net (code "87") (name "Net-(U4-QE)") (class "Default")
      (node (ref "U4") (pin "4") (pinfunction "QE_4") (pintype "unspecified"))
      (node (ref "U6") (pin "3") (pinfunction "A_3") (pintype "input"))
    )
    (net (code "88") (name "Net-(U4-QF)") (class "Default")
      (node (ref "U4") (pin "5") (pinfunction "QF_5") (pintype "unspecified"))
      (node (ref "U6") (pin "6") (pinfunction "B_6") (pintype "input"))
    )
    (net (code "89") (name "Net-(U4-QG)") (class "Default")
      (node (ref "U4") (pin "6") (pinfunction "QG_6") (pintype "unspecified"))
      (node (ref "U6") (pin "7") (pinfunction "C_7") (pintype "input"))
    )
    (net (code "90") (name "Net-(U4-QH)") (class "Default")
      (node (ref "U4") (pin "7") (pinfunction "QH_7") (pintype "unspecified"))
      (node (ref "U6") (pin "4") (pinfunction "D_4") (pintype "input"))
    )
    (net (code "91") (name "Net-(U5-0)") (class "Default")
      (node (ref "N3") (pin "0") (pinfunction "0_0") (pintype "unspecified"))
      (node (ref "U5") (pin "16") (pinfunction "0_16") (pintype "output"))
    )
    (net (code "92") (name "Net-(U5-1)") (class "Default")
      (node (ref "N3") (pin "1") (pinfunction "1_1") (pintype "unspecified"))
      (node (ref "U5") (pin "15") (pinfunction "1_15") (pintype "output"))
    )
    (net (code "93") (name "Net-(U5-2)") (class "Default")
      (node (ref "N3") (pin "2") (pinfunction "2_2") (pintype "unspecified"))
      (node (ref "U5") (pin "8") (pinfunction "2_8") (pintype "output"))
    )
    (net (code "94") (name "Net-(U5-3)") (class "Default")
      (node (ref "N3") (pin "3") (pinfunction "3_3") (pintype "unspecified"))
      (node (ref "U5") (pin "9") (pinfunction "3_9") (pintype "output"))
    )
    (net (code "95") (name "Net-(U5-4)") (class "Default")
      (node (ref "N3") (pin "4") (pinfunction "4_4") (pintype "unspecified"))
      (node (ref "U5") (pin "13") (pinfunction "4_13") (pintype "output"))
    )
    (net (code "96") (name "Net-(U5-5)") (class "Default")
      (node (ref "N3") (pin "5") (pinfunction "5_5") (pintype "unspecified"))
      (node (ref "U5") (pin "14") (pinfunction "5_14") (pintype "output"))
    )
    (net (code "97") (name "Net-(U5-6)") (class "Default")
      (node (ref "N3") (pin "6") (pinfunction "6_6") (pintype "unspecified"))
      (node (ref "U5") (pin "11") (pinfunction "6_11") (pintype "output"))
    )
    (net (code "98") (name "Net-(U5-7)") (class "Default")
      (node (ref "N3") (pin "7") (pinfunction "7_7") (pintype "unspecified"))
      (node (ref "U5") (pin "10") (pinfunction "7_10") (pintype "output"))
    )
    (net (code "99") (name "Net-(U5-8)") (class "Default")
      (node (ref "N3") (pin "8") (pinfunction "8_8") (pintype "unspecified"))
      (node (ref "U5") (pin "1") (pinfunction "8_1") (pintype "output"))
    )
    (net (code "100") (name "Net-(U5-9)") (class "Default")
      (node (ref "N3") (pin "9") (pinfunction "9_9") (pintype "unspecified"))
      (node (ref "U5") (pin "2") (pinfunction "9_2") (pintype "output"))
    )
    (net (code "101") (name "Net-(U6-0)") (class "Default")
      (node (ref "N4") (pin "0") (pinfunction "0_0") (pintype "unspecified"))
      (node (ref "U6") (pin "16") (pinfunction "0_16") (pintype "output"))
    )
    (net (code "102") (name "Net-(U6-1)") (class "Default")
      (node (ref "N4") (pin "1") (pinfunction "1_1") (pintype "unspecified"))
      (node (ref "U6") (pin "15") (pinfunction "1_15") (pintype "output"))
    )
    (net (code "103") (name "Net-(U6-2)") (class "Default")
      (node (ref "N4") (pin "2") (pinfunction "2_2") (pintype "unspecified"))
      (node (ref "U6") (pin "8") (pinfunction "2_8") (pintype "output"))
    )
    (net (code "104") (name "Net-(U6-3)") (class "Default")
      (node (ref "N4") (pin "3") (pinfunction "3_3") (pintype "unspecified"))
      (node (ref "U6") (pin "9") (pinfunction "3_9") (pintype "output"))
    )
    (net (code "105") (name "Net-(U6-4)") (class "Default")
      (node (ref "N4") (pin "4") (pinfunction "4_4") (pintype "unspecified"))
      (node (ref "U6") (pin "13") (pinfunction "4_13") (pintype "output"))
    )
    (net (code "106") (name "Net-(U6-5)") (class "Default")
      (node (ref "N4") (pin "5") (pinfunction "5_5") (pintype "unspecified"))
      (node (ref "U6") (pin "14") (pinfunction "5_14") (pintype "output"))
    )
    (net (code "107") (name "Net-(U6-6)") (class "Default")
      (node (ref "N4") (pin "6") (pinfunction "6_6") (pintype "unspecified"))
      (node (ref "U6") (pin "11") (pinfunction "6_11") (pintype "output"))
    )
    (net (code "108") (name "Net-(U6-7)") (class "Default")
      (node (ref "N4") (pin "7") (pinfunction "7_7") (pintype "unspecified"))
      (node (ref "U6") (pin "10") (pinfunction "7_10") (pintype "output"))
    )
    (net (code "109") (name "Net-(U6-8)") (class "Default")
      (node (ref "N4") (pin "8") (pinfunction "8_8") (pintype "unspecified"))
      (node (ref "U6") (pin "1") (pinfunction "8_1") (pintype "output"))
    )
    (net (code "110") (name "Net-(U6-9)") (class "Default")
      (node (ref "N4") (pin "9") (pinfunction "9_9") (pintype "unspecified"))
      (node (ref "U6") (pin "2") (pinfunction "9_2") (pintype "output"))
    )
    (net (code "111") (name "Net-(U7-QA)") (class "Default")
      (node (ref "U7") (pin "15") (pinfunction "QA_15") (pintype "unspecified"))
      (node (ref "U8") (pin "3") (pinfunction "A_3") (pintype "input"))
    )
    (net (code "112") (name "Net-(U7-QB)") (class "Default")
      (node (ref "U7") (pin "1") (pinfunction "QB_1") (pintype "unspecified"))
      (node (ref "U8") (pin "6") (pinfunction "B_6") (pintype "input"))
    )
    (net (code "113") (name "Net-(U7-QC)") (class "Default")
      (node (ref "U7") (pin "2") (pinfunction "QC_2") (pintype "unspecified"))
      (node (ref "U8") (pin "7") (pinfunction "C_7") (pintype "input"))
    )
    (net (code "114") (name "Net-(U7-QD)") (class "Default")
      (node (ref "U7") (pin "3") (pinfunction "QD_3") (pintype "unspecified"))
      (node (ref "U8") (pin "4") (pinfunction "D_4") (pintype "input"))
    )
    (net (code "115") (name "Net-(U7-QE)") (class "Default")
      (node (ref "U7") (pin "4") (pinfunction "QE_4") (pintype "unspecified"))
      (node (ref "U9") (pin "3") (pinfunction "A_3") (pintype "input"))
    )
    (net (code "116") (name "Net-(U7-QF)") (class "Default")
      (node (ref "U7") (pin "5") (pinfunction "QF_5") (pintype "unspecified"))
      (node (ref "U9") (pin "6") (pinfunction "B_6") (pintype "input"))
    )
    (net (code "117") (name "Net-(U7-QG)") (class "Default")
      (node (ref "U7") (pin "6") (pinfunction "QG_6") (pintype "unspecified"))
      (node (ref "U9") (pin "7") (pinfunction "C_7") (pintype "input"))
    )
    (net (code "118") (name "Net-(U7-QH)") (class "Default")
      (node (ref "U7") (pin "7") (pinfunction "QH_7") (pintype "unspecified"))
      (node (ref "U9") (pin "4") (pinfunction "D_4") (pintype "input"))
    )
    (net (code "119") (name "Net-(U8-0)") (class "Default")
      (node (ref "N5") (pin "0") (pinfunction "0_0") (pintype "unspecified"))
      (node (ref "U8") (pin "16") (pinfunction "0_16") (pintype "output"))
    )
    (net (code "120") (name "Net-(U8-1)") (class "Default")
      (node (ref "N5") (pin "1") (pinfunction "1_1") (pintype "unspecified"))
      (node (ref "U8") (pin "15") (pinfunction "1_15") (pintype "output"))
    )
    (net (code "121") (name "Net-(U8-2)") (class "Default")
      (node (ref "N5") (pin "2") (pinfunction "2_2") (pintype "unspecified"))
      (node (ref "U8") (pin "8") (pinfunction "2_8") (pintype "output"))
    )
    (net (code "122") (name "Net-(U8-3)") (class "Default")
      (node (ref "N5") (pin "3") (pinfunction "3_3") (pintype "unspecified"))
      (node (ref "U8") (pin "9") (pinfunction "3_9") (pintype "output"))
    )
    (net (code "123") (name "Net-(U8-4)") (class "Default")
      (node (ref "N5") (pin "4") (pinfunction "4_4") (pintype "unspecified"))
      (node (ref "U8") (pin "13") (pinfunction "4_13") (pintype "output"))
    )
    (net (code "124") (name "Net-(U8-5)") (class "Default")
      (node (ref "N5") (pin "5") (pinfunction "5_5") (pintype "unspecified"))
      (node (ref "U8") (pin "14") (pinfunction "5_14") (pintype "output"))
    )
    (net (code "125") (name "Net-(U8-6)") (class "Default")
      (node (ref "N5") (pin "6") (pinfunction "6_6") (pintype "unspecified"))
      (node (ref "U8") (pin "11") (pinfunction "6_11") (pintype "output"))
    )
    (net (code "126") (name "Net-(U8-7)") (class "Default")
      (node (ref "N5") (pin "7") (pinfunction "7_7") (pintype "unspecified"))
      (node (ref "U8") (pin "10") (pinfunction "7_10") (pintype "output"))
    )
    (net (code "127") (name "Net-(U8-8)") (class "Default")
      (node (ref "N5") (pin "8") (pinfunction "8_8") (pintype "unspecified"))
      (node (ref "U8") (pin "1") (pinfunction "8_1") (pintype "output"))
    )
    (net (code "128") (name "Net-(U8-9)") (class "Default")
      (node (ref "N5") (pin "9") (pinfunction "9_9") (pintype "unspecified"))
      (node (ref "U8") (pin "2") (pinfunction "9_2") (pintype "output"))
    )
    (net (code "129") (name "Net-(U9-0)") (class "Default")
      (node (ref "N6") (pin "0") (pinfunction "0_0") (pintype "unspecified"))
      (node (ref "U9") (pin "16") (pinfunction "0_16") (pintype "output"))
    )
    (net (code "130") (name "Net-(U9-1)") (class "Default")
      (node (ref "N6") (pin "1") (pinfunction "1_1") (pintype "unspecified"))
      (node (ref "U9") (pin "15") (pinfunction "1_15") (pintype "output"))
    )
    (net (code "131") (name "Net-(U9-2)") (class "Default")
      (node (ref "N6") (pin "2") (pinfunction "2_2") (pintype "unspecified"))
      (node (ref "U9") (pin "8") (pinfunction "2_8") (pintype "output"))
    )
    (net (code "132") (name "Net-(U9-3)") (class "Default")
      (node (ref "N6") (pin "3") (pinfunction "3_3") (pintype "unspecified"))
      (node (ref "U9") (pin "9") (pinfunction "3_9") (pintype "output"))
    )
    (net (code "133") (name "Net-(U9-4)") (class "Default")
      (node (ref "N6") (pin "4") (pinfunction "4_4") (pintype "unspecified"))
      (node (ref "U9") (pin "13") (pinfunction "4_13") (pintype "output"))
    )
    (net (code "134") (name "Net-(U9-5)") (class "Default")
      (node (ref "N6") (pin "5") (pinfunction "5_5") (pintype "unspecified"))
      (node (ref "U9") (pin "14") (pinfunction "5_14") (pintype "output"))
    )
    (net (code "135") (name "Net-(U9-6)") (class "Default")
      (node (ref "N6") (pin "6") (pinfunction "6_6") (pintype "unspecified"))
      (node (ref "U9") (pin "11") (pinfunction "6_11") (pintype "output"))
    )
    (net (code "136") (name "Net-(U9-7)") (class "Default")
      (node (ref "N6") (pin "7") (pinfunction "7_7") (pintype "unspecified"))
      (node (ref "U9") (pin "10") (pinfunction "7_10") (pintype "output"))
    )
    (net (code "137") (name "Net-(U9-8)") (class "Default")
      (node (ref "N6") (pin "8") (pinfunction "8_8") (pintype "unspecified"))
      (node (ref "U9") (pin "1") (pinfunction "8_1") (pintype "output"))
    )
    (net (code "138") (name "Net-(U9-9)") (class "Default")
      (node (ref "N6") (pin "9") (pinfunction "9_9") (pintype "unspecified"))
      (node (ref "U9") (pin "2") (pinfunction "9_2") (pintype "output"))
    )
    (net (code "139") (name "Net-(U11-VOUT)") (class "Default")
      (node (ref "C7") (pin "1") (pinfunction "1_1") (pintype "unspecified"))
      (node (ref "U11") (pin "2") (pinfunction "VOUT_2") (pintype "unspecified"))
    )
    (net (code "140") (name "Net-(U12-COMP)") (class "Default")
      (node (ref "R12") (pin "1") (pinfunction "1_1") (pintype "input"))
      (node (ref "R13") (pin "2") (pinfunction "2_2") (pintype "input"))
      (node (ref "U12") (pin "5") (pinfunction "COMP_5") (pintype "unspecified"))
    )
    (net (code "141") (name "Net-(U12-DVR)") (class "Default")
      (node (ref "R11") (pin "2") (pinfunction "2_2") (pintype "unspecified"))
      (node (ref "U12") (pin "8") (pinfunction "DVR_8") (pintype "unspecified"))
    )
    (net (code "142") (name "Net-(U12-SEN)") (class "Default")
      (node (ref "L1") (pin "1") (pinfunction "1_1") (pintype "unspecified"))
      (node (ref "R11") (pin "1") (pinfunction "1_1") (pintype "unspecified"))
      (node (ref "R9") (pin "2") (pinfunction "2_2") (pintype "unspecified"))
      (node (ref "U12") (pin "1") (pinfunction "SWC_1") (pintype "unspecified"))
      (node (ref "U12") (pin "7") (pinfunction "SEN_7") (pintype "unspecified"))
    )
    (net (code "143") (name "Net-(U12-TC)") (class "Default")
      (node (ref "C2") (pin "1") (pinfunction "1_1") (pintype "unspecified"))
      (node (ref "U12") (pin "3") (pinfunction "TC_3") (pintype "unspecified"))
    )
    (net (code "144") (name "OUT0") (class "Default")
      (node (ref "H1") (pin "10") (pinfunction "14_10") (pintype "unspecified"))
      (node (ref "LED1") (pin "4") (pinfunction "DIN_4") (pintype "unspecified"))
    )
    (net (code "145") (name "OUT1") (class "Default")
      (node (ref "LED1") (pin "2") (pinfunction "DOUT_2") (pintype "unspecified"))
      (node (ref "LED2") (pin "4") (pinfunction "DIN_4") (pintype "unspecified"))
    )
    (net (code "146") (name "OUT2") (class "Default")
      (node (ref "LED2") (pin "2") (pinfunction "DOUT_2") (pintype "unspecified"))
      (node (ref "LED3") (pin "4") (pinfunction "DIN_4") (pintype "unspecified"))
    )
    (net (code "147") (name "OUT3") (class "Default")
      (node (ref "LED3") (pin "2") (pinfunction "DOUT_2") (pintype "unspecified"))
      (node (ref "LED6") (pin "2") (pinfunction "DOUT_2") (pintype "unspecified"))
    )
    (net (code "148") (name "OUT4") (class "Default")
      (node (ref "LED5") (pin "4") (pinfunction "DIN_4") (pintype "unspecified"))
      (node (ref "LED6") (pin "4") (pinfunction "DIN_4") (pintype "unspecified"))
    )
    (net (code "149") (name "OUT5") (class "Default")
      (node (ref "LED4") (pin "4") (pinfunction "DIN_4") (pintype "unspecified"))
      (node (ref "LED5") (pin "2") (pinfunction "DOUT_2") (pintype "unspecified"))
    )
    (net (code "150") (name "S1DATA") (class "Default")
      (node (ref "U1") (pin "9") (pinfunction "QH'_9") (pintype "unspecified"))
    )
    (net (code "151") (name "S2DATA") (class "Default")
      (node (ref "U4") (pin "14") (pinfunction "SI_14") (pintype "unspecified"))
      (node (ref "U4") (pin "9") (pinfunction "QH'_9") (pintype "unspecified"))
      (node (ref "U7") (pin "14") (pinfunction "SI_14") (pintype "unspecified"))
    )
    (net (code "152") (name "SDA") (class "Default")
      (node (ref "H1") (pin "7") (pinfunction "32_7") (pintype "unspecified"))
    )
    (net (code "153") (name "SDL") (class "Default")
      (node (ref "H1") (pin "8") (pinfunction "25_8") (pintype "unspecified"))
    )
    (net (code "154") (name "VCC") (class "Default")
      (node (ref "LED1") (pin "1") (pinfunction "VDD_1") (pintype "unspecified"))
      (node (ref "LED2") (pin "1") (pinfunction "VDD_1") (pintype "unspecified"))
      (node (ref "LED3") (pin "1") (pinfunction "VDD_1") (pintype "unspecified"))
      (node (ref "LED4") (pin "1") (pinfunction "VDD_1") (pintype "unspecified"))
      (node (ref "LED5") (pin "1") (pinfunction "VDD_1") (pintype "unspecified"))
      (node (ref "LED6") (pin "1") (pinfunction "VDD_1") (pintype "unspecified"))
      (node (ref "U12") (pin "6") (pinfunction "VCC_6") (pintype "unspecified"))
    )
    (net (code "155") (name "VSPI MOSI") (class "Default")
      (node (ref "U1") (pin "14") (pinfunction "SI_14") (pintype "unspecified"))
    )
    (net (code "156") (name "unconnected-(H1-EN-Pad15)") (class "Default")
      (node (ref "H1") (pin "15") (pinfunction "EN_15") (pintype "unspecified"))
    )
    (net (code "157") (name "unconnected-(H2-2-Pad4)") (class "Default")
      (node (ref "H2") (pin "4") (pinfunction "2_4") (pintype "unspecified"))
    )
    (net (code "158") (name "unconnected-(H2-4-Pad5)") (class "Default")
      (node (ref "H2") (pin "5") (pinfunction "4_5") (pintype "unspecified"))
    )
    (net (code "159") (name "unconnected-(H2-5-Pad8)") (class "Default")
      (node (ref "H2") (pin "8") (pinfunction "5_8") (pintype "unspecified"))
    )
    (net (code "160") (name "unconnected-(H2-23-Pad15)") (class "Default")
      (node (ref "H2") (pin "15") (pinfunction "23_15") (pintype "unspecified"))
    )
    (net (code "161") (name "unconnected-(H2-RX2-Pad6)") (class "Default")
      (node (ref "H2") (pin "6") (pinfunction "RX2_6") (pintype "unspecified"))
    )
    (net (code "162") (name "unconnected-(H2-TX2-Pad7)") (class "Default")
      (node (ref "H2") (pin "7") (pinfunction "TX2_7") (pintype "unspecified"))
    )
    (net (code "163") (name "unconnected-(LED4-DOUT-Pad2)") (class "Default")
      (node (ref "LED4") (pin "2") (pinfunction "DOUT_2") (pintype "unspecified"))
    )
    (net (code "164") (name "unconnected-(U7-QH'-Pad9)") (class "Default")
      (node (ref "U7") (pin "9") (pinfunction "QH'_9") (pintype "unspecified"))
    )
    (net (code "165") (name "unconnected-(U10-Pad2)") (class "Default")
      (node (ref "U10") (pin "2") (pinfunction "2_2") (pintype "unspecified"))
    )
  )
)
